# altium_no_connect.net
KiCad netlist of a schematic drawn in Altium Designer
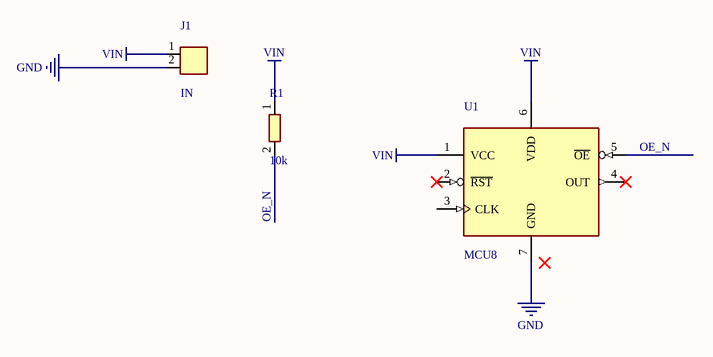
[diagram p0: altium_no_connect.SchDoc]

(export (version "E")
  (design (tool "Eeschema 10.0.6"))
  (components
    (comp (ref "J1")
      (value "IN")
      (footprint "altium_no_connect:PinHeader_1x02")
      (libsource (lib "altium_no_connect") (part "CONN2"))
    )
    (comp (ref "R1")
      (value "10k")
      (footprint "altium_no_connect:R0603")
      (libsource (lib "altium_no_connect") (part "R_V"))
    )
    (comp (ref "U1")
      (value "MCU8")
      (footprint "altium_no_connect:SOIC8")
      (libsource (lib "altium_no_connect") (part "MCU8"))
    )
  )
  (nets
    (net (code "1") (name "/OE_N") (class "Default")
      (node (ref "R1") (pin "2") (pinfunction "~_2") (pintype "passive"))
      (node (ref "U1") (pin "5") (pinfunction "~{OE}_5") (pintype "input"))
    )
    (net (code "2") (name "GND") (class "Default")
      (node (ref "J1") (pin "2") (pinfunction "2_2") (pintype "passive"))
      (node (ref "U1") (pin "7") (pinfunction "GND_7") (pintype "power_in"))
    )
    (net (code "3") (name "VIN") (class "Default")
      (node (ref "J1") (pin "1") (pinfunction "1_1") (pintype "passive"))
      (node (ref "R1") (pin "1") (pinfunction "~_1") (pintype "passive"))
      (node (ref "U1") (pin "1") (pinfunction "VCC_1") (pintype "power_in"))
      (node (ref "U1") (pin "6") (pinfunction "VDD_6") (pintype "power_in"))
    )
    (net (code "4") (name "unconnected-(U1-CLK-Pad3)") (class "Default")
      (node (ref "U1") (pin "3") (pinfunction "CLK_3") (pintype "input"))
    )
    (net (code "5") (name "unconnected-(U1-OUT-Pad4)") (class "Default")
      (node (ref "U1") (pin "4") (pinfunction "OUT_4") (pintype "output+no_connect"))
    )
    (net (code "6") (name "unconnected-(U1-TP-Pad8)") (class "Default")
      (node (ref "U1") (pin "8") (pinfunction "TP_8") (pintype "passive+no_connect"))
    )
    (net (code "7") (name "unconnected-(U1-~{RST}-Pad2)") (class "Default")
      (node (ref "U1") (pin "2") (pinfunction "~{RST}_2") (pintype "input+no_connect"))
    )
  )
)
